# PCBV3.net
KiCad netlist of a schematic drawn in EAGLE
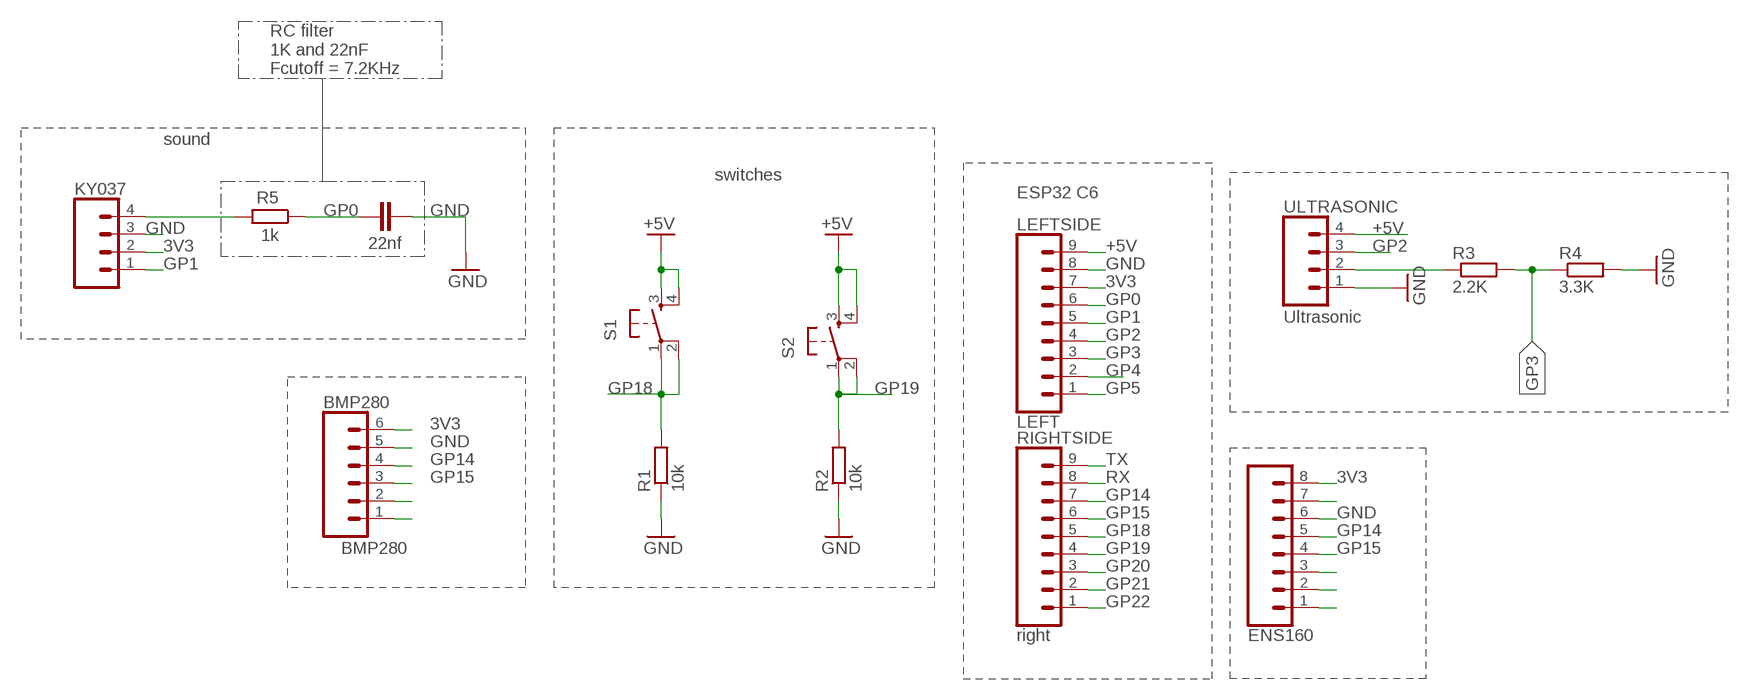
[diagram p0: schematic, sheet 1]

(export (version "E")
  (design (tool "Eeschema 10.0.6"))
  (components
    (comp (ref "BMP280")
      (value "BMP280")
      (footprint "eagle-import:SPARKFUN-CONNECTORS_1X06_LONGPADS")
      (libsource (lib "eagle-import") (part "SPARKFUN-CONNECTORS_CONN_06LONGPADS"))
    )
    (comp (ref "C1")
      (value "22nf")
      (footprint "eagle-import:CAPACITOR-WIMA_C2.5-2")
      (libsource (lib "eagle-import") (part "CAPACITOR-WIMA_C2.5/2"))
    )
    (comp (ref "J3")
      (value "ENS160")
      (footprint "eagle-import:1X08")
      (libsource (lib "eagle-import") (part "CONN_08{dblquote}"))
    )
    (comp (ref "KY037")
      (value "1X04_SMD_STRAIGHT_COMBO")
      (footprint "eagle-import:1X04_LONGPADS")
      (libsource (lib "eagle-import") (part "CONN_04LONGPADS"))
    )
    (comp (ref "LEFTSIDE")
      (value "LEFT")
      (footprint "eagle-import:1X09")
      (libsource (lib "eagle-import") (part "CONN_09"))
    )
    (comp (ref "R1")
      (value "10k")
      (footprint "eagle-import:0207_10")
      (libsource (lib "eagle-import") (part "R-EU_0207/10"))
    )
    (comp (ref "R2")
      (value "10k")
      (footprint "eagle-import:0207_10")
      (libsource (lib "eagle-import") (part "R-EU_0207/10"))
    )
    (comp (ref "R3")
      (value "2.2K")
      (footprint "eagle-import:0207_10")
      (libsource (lib "eagle-import") (part "R-EU_0207/10"))
    )
    (comp (ref "R4")
      (value "3.3K")
      (footprint "eagle-import:0207_10")
      (libsource (lib "eagle-import") (part "R-EU_0207/10"))
    )
    (comp (ref "R5")
      (value "1k")
      (footprint "eagle-import:0207_10")
      (libsource (lib "eagle-import") (part "R-EU_0207/10"))
    )
    (comp (ref "RIGHTSIDE")
      (value "right")
      (footprint "eagle-import:1X09")
      (libsource (lib "eagle-import") (part "CONN_09"))
    )
    (comp (ref "S1")
      (value "EL311-ROBOT_SPARKFUN-ELECTROMECHANICAL_TAC_SWITCHPTH")
      (footprint "eagle-import:EL311-ROBOT_SPARKFUN-ELECTROMECHANICAL_TACTILE-PTH")
      (libsource (lib "eagle-import") (part "EL311-ROBOT_SPARKFUN-ELECTROMECHANICAL_TAC_SWITCHPTH"))
    )
    (comp (ref "S2")
      (value "EL311-ROBOT_SPARKFUN-ELECTROMECHANICAL_TAC_SWITCHPTH")
      (footprint "eagle-import:EL311-ROBOT_SPARKFUN-ELECTROMECHANICAL_TACTILE-PTH")
      (libsource (lib "eagle-import") (part "EL311-ROBOT_SPARKFUN-ELECTROMECHANICAL_TAC_SWITCHPTH"))
    )
    (comp (ref "ULTRASONIC")
      (value "1X04_SMD_STRAIGHT_COMBO")
      (footprint "eagle-import:1X04_LONGPADS")
      (libsource (lib "eagle-import") (part "CONN_04LONGPADS"))
    )
  )
  (nets
    (net (code "1") (name "+5V") (class "Default")
      (node (ref "LEFTSIDE") (pin "9") (pinfunction "9_9") (pintype "passive"))
      (node (ref "S1") (pin "3") (pinfunction "3_3") (pintype "passive"))
      (node (ref "S1") (pin "4") (pinfunction "4_4") (pintype "passive"))
      (node (ref "S2") (pin "3") (pinfunction "3_3") (pintype "passive"))
      (node (ref "S2") (pin "4") (pinfunction "4_4") (pintype "passive"))
      (node (ref "ULTRASONIC") (pin "4") (pinfunction "4_4") (pintype "passive"))
    )
    (net (code "2") (name "/3V3") (class "Default")
      (node (ref "BMP280") (pin "6") (pinfunction "6_6") (pintype "passive"))
      (node (ref "J3") (pin "8") (pinfunction "8_8") (pintype "passive"))
      (node (ref "KY037") (pin "2") (pinfunction "2_2") (pintype "passive"))
      (node (ref "LEFTSIDE") (pin "7") (pinfunction "7_7") (pintype "passive"))
    )
    (net (code "3") (name "/GP0") (class "Default")
      (node (ref "C1") (pin "1") (pinfunction "1_1") (pintype "passive"))
      (node (ref "LEFTSIDE") (pin "6") (pinfunction "6_6") (pintype "passive"))
      (node (ref "R5") (pin "1") (pinfunction "1_1") (pintype "passive"))
    )
    (net (code "4") (name "/GP1") (class "Default")
      (node (ref "KY037") (pin "1") (pinfunction "1_1") (pintype "passive"))
      (node (ref "LEFTSIDE") (pin "5") (pinfunction "5_5") (pintype "passive"))
    )
    (net (code "5") (name "/GP2") (class "Default")
      (node (ref "LEFTSIDE") (pin "4") (pinfunction "4_4") (pintype "passive"))
      (node (ref "ULTRASONIC") (pin "3") (pinfunction "3_3") (pintype "passive"))
    )
    (net (code "6") (name "/GP4") (class "Default")
      (node (ref "LEFTSIDE") (pin "2") (pinfunction "2_2") (pintype "passive"))
    )
    (net (code "7") (name "/GP5") (class "Default")
      (node (ref "LEFTSIDE") (pin "1") (pinfunction "1_1") (pintype "passive"))
    )
    (net (code "8") (name "/GP14") (class "Default")
      (node (ref "BMP280") (pin "4") (pinfunction "4_4") (pintype "passive"))
      (node (ref "J3") (pin "5") (pinfunction "5_5") (pintype "passive"))
      (node (ref "RIGHTSIDE") (pin "7") (pinfunction "7_7") (pintype "passive"))
    )
    (net (code "9") (name "/GP15") (class "Default")
      (node (ref "BMP280") (pin "3") (pinfunction "3_3") (pintype "passive"))
      (node (ref "J3") (pin "4") (pinfunction "4_4") (pintype "passive"))
      (node (ref "RIGHTSIDE") (pin "6") (pinfunction "6_6") (pintype "passive"))
    )
    (net (code "10") (name "/GP18") (class "Default")
      (node (ref "R1") (pin "2") (pinfunction "2_2") (pintype "passive"))
      (node (ref "RIGHTSIDE") (pin "5") (pinfunction "5_5") (pintype "passive"))
      (node (ref "S1") (pin "1") (pinfunction "1_1") (pintype "passive"))
      (node (ref "S1") (pin "2") (pinfunction "2_2") (pintype "passive"))
    )
    (net (code "11") (name "/GP19") (class "Default")
      (node (ref "R2") (pin "2") (pinfunction "2_2") (pintype "passive"))
      (node (ref "RIGHTSIDE") (pin "4") (pinfunction "4_4") (pintype "passive"))
      (node (ref "S2") (pin "1") (pinfunction "1_1") (pintype "passive"))
      (node (ref "S2") (pin "2") (pinfunction "2_2") (pintype "passive"))
    )
    (net (code "12") (name "/GP20") (class "Default")
      (node (ref "RIGHTSIDE") (pin "3") (pinfunction "3_3") (pintype "passive"))
    )
    (net (code "13") (name "/GP21") (class "Default")
      (node (ref "RIGHTSIDE") (pin "2") (pinfunction "2_2") (pintype "passive"))
    )
    (net (code "14") (name "/GP22") (class "Default")
      (node (ref "RIGHTSIDE") (pin "1") (pinfunction "1_1") (pintype "passive"))
    )
    (net (code "15") (name "/RX") (class "Default")
      (node (ref "RIGHTSIDE") (pin "8") (pinfunction "8_8") (pintype "passive"))
    )
    (net (code "16") (name "/TX") (class "Default")
      (node (ref "RIGHTSIDE") (pin "9") (pinfunction "9_9") (pintype "passive"))
    )
    (net (code "17") (name "GND") (class "Default")
      (node (ref "BMP280") (pin "5") (pinfunction "5_5") (pintype "passive"))
      (node (ref "C1") (pin "2") (pinfunction "2_2") (pintype "passive"))
      (node (ref "J3") (pin "6") (pinfunction "6_6") (pintype "passive"))
      (node (ref "KY037") (pin "3") (pinfunction "3_3") (pintype "passive"))
      (node (ref "LEFTSIDE") (pin "8") (pinfunction "8_8") (pintype "passive"))
      (node (ref "R1") (pin "1") (pinfunction "1_1") (pintype "passive"))
      (node (ref "R2") (pin "1") (pinfunction "1_1") (pintype "passive"))
      (node (ref "R4") (pin "2") (pinfunction "2_2") (pintype "passive"))
      (node (ref "ULTRASONIC") (pin "1") (pinfunction "1_1") (pintype "passive"))
    )
    (net (code "18") (name "GP3") (class "Default")
      (node (ref "LEFTSIDE") (pin "3") (pinfunction "3_3") (pintype "passive"))
      (node (ref "R3") (pin "2") (pinfunction "2_2") (pintype "passive"))
      (node (ref "R4") (pin "1") (pinfunction "1_1") (pintype "passive"))
    )
    (net (code "19") (name "Net-(KY037-Pad4)") (class "Default")
      (node (ref "KY037") (pin "4") (pinfunction "4_4") (pintype "passive"))
      (node (ref "R5") (pin "2") (pinfunction "2_2") (pintype "passive"))
    )
    (net (code "20") (name "Net-(R3-Pad1)") (class "Default")
      (node (ref "R3") (pin "1") (pinfunction "1_1") (pintype "passive"))
      (node (ref "ULTRASONIC") (pin "2") (pinfunction "2_2") (pintype "passive"))
    )
    (net (code "21") (name "unconnected-(BMP280-Pad1)") (class "Default")
      (node (ref "BMP280") (pin "1") (pinfunction "1_1") (pintype "passive"))
    )
    (net (code "22") (name "unconnected-(BMP280-Pad2)") (class "Default")
      (node (ref "BMP280") (pin "2") (pinfunction "2_2") (pintype "passive"))
    )
    (net (code "23") (name "unconnected-(J3-Pad1)") (class "Default")
      (node (ref "J3") (pin "1") (pinfunction "1_1") (pintype "passive"))
    )
    (net (code "24") (name "unconnected-(J3-Pad2)") (class "Default")
      (node (ref "J3") (pin "2") (pinfunction "2_2") (pintype "passive"))
    )
    (net (code "25") (name "unconnected-(J3-Pad3)") (class "Default")
      (node (ref "J3") (pin "3") (pinfunction "3_3") (pintype "passive"))
    )
    (net (code "26") (name "unconnected-(J3-Pad7)") (class "Default")
      (node (ref "J3") (pin "7") (pinfunction "7_7") (pintype "passive"))
    )
  )
)
